# Controller.net
KiCad netlist of a schematic drawn in Altium Designer
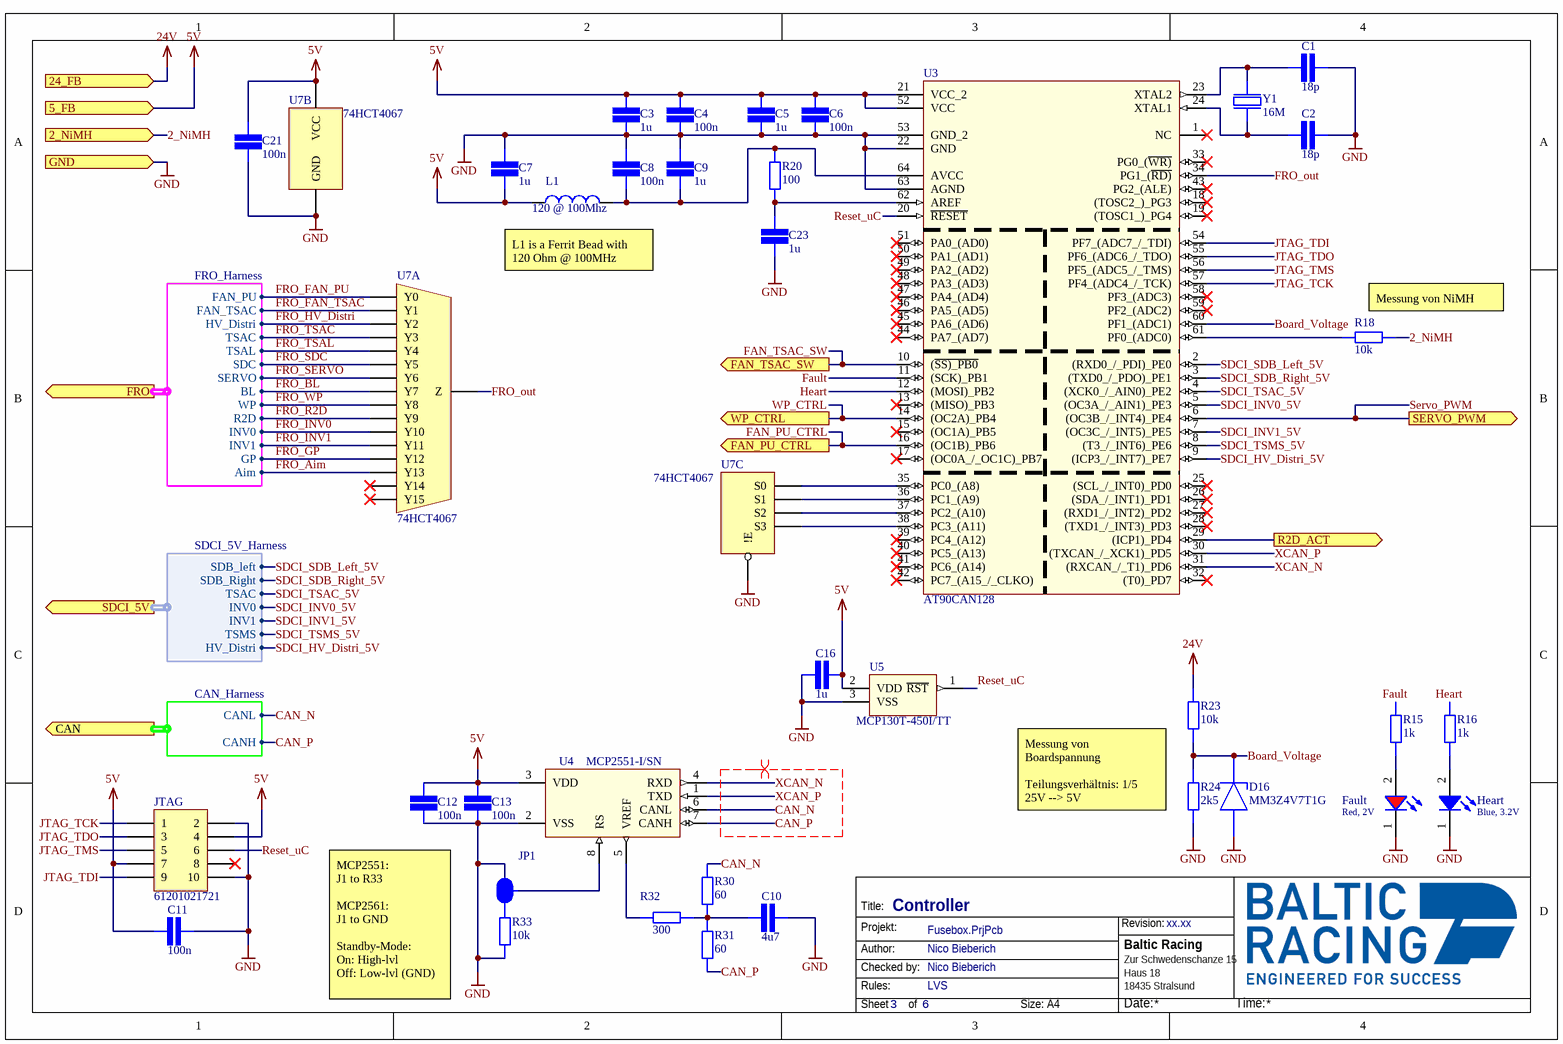
[diagram p0: Controller.SchDoc]

(export (version "E")
  (design (tool "Eeschema 10.0.6"))
  (components
    (comp (ref "C1")
      (value "18p")
      (footprint "CAP 0603/1608")
      (description "Capacitor with multiple Footprints")
      (fields (field (name "VOLTAGE") "16") (field (name "Comment") "SMD Capacitor"))
      (libsource (lib "") (part "SMD Capacitor_1"))
    )
    (comp (ref "C2")
      (value "18p")
      (footprint "CAP 0603/1608")
      (description "Capacitor with multiple Footprints")
      (fields (field (name "VOLTAGE") "16") (field (name "Comment") "SMD Capacitor"))
      (libsource (lib "") (part "SMD Capacitor_1"))
    )
    (comp (ref "C3")
      (value "1u")
      (footprint "CAP 0603/1608")
      (description "Capacitor with multiple Footprints")
      (fields (field (name "VOLTAGE") "16") (field (name "Comment") "SMD Capacitor"))
      (libsource (lib "Standardbauteile") (part "SMD Capacitor"))
    )
    (comp (ref "C4")
      (value "100n")
      (footprint "CAP 0603/1608")
      (description "Capacitor with multiple Footprints")
      (fields (field (name "VOLTAGE") "16") (field (name "Comment") "SMD Capacitor"))
      (libsource (lib "Standardbauteile") (part "SMD Capacitor"))
    )
    (comp (ref "C5")
      (value "1u")
      (footprint "CAP 0603/1608")
      (description "Capacitor with multiple Footprints")
      (fields (field (name "VOLTAGE") "16") (field (name "Comment") "SMD Capacitor"))
      (libsource (lib "Standardbauteile") (part "SMD Capacitor"))
    )
    (comp (ref "C6")
      (value "100n")
      (footprint "CAP 0603/1608")
      (description "Capacitor with multiple Footprints")
      (fields (field (name "VOLTAGE") "16") (field (name "Comment") "SMD Capacitor"))
      (libsource (lib "Standardbauteile") (part "SMD Capacitor"))
    )
    (comp (ref "C7")
      (value "1u")
      (footprint "CAP 0603/1608")
      (description "Capacitor with multiple Footprints")
      (fields (field (name "VOLTAGE") "16") (field (name "Comment") "SMD Capacitor"))
      (libsource (lib "Standardbauteile") (part "SMD Capacitor"))
    )
    (comp (ref "C8")
      (value "100n")
      (footprint "CAP 0603/1608")
      (description "Capacitor with multiple Footprints")
      (fields (field (name "VOLTAGE") "16") (field (name "Comment") "SMD Capacitor"))
      (libsource (lib "Standardbauteile") (part "SMD Capacitor"))
    )
    (comp (ref "C9")
      (value "1u")
      (footprint "CAP 0603/1608")
      (description "Capacitor with multiple Footprints")
      (fields (field (name "VOLTAGE") "16") (field (name "Comment") "SMD Capacitor"))
      (libsource (lib "Standardbauteile") (part "SMD Capacitor"))
    )
    (comp (ref "C10")
      (value "4u7")
      (footprint "CAP 0603/1608")
      (description "Capacitor with multiple Footprints")
      (fields (field (name "VOLTAGE") "16") (field (name "Comment") "SMD Capacitor"))
      (libsource (lib "") (part "SMD Capacitor_2"))
    )
    (comp (ref "C11")
      (value "100n")
      (footprint "CAP 0603/1608")
      (description "Capacitor with multiple Footprints")
      (fields (field (name "VOLTAGE") "16") (field (name "Comment") "SMD Capacitor"))
      (libsource (lib "") (part "SMD Capacitor_1"))
    )
    (comp (ref "C12")
      (value "100n")
      (footprint "CAP 0603/1608")
      (description "Capacitor with multiple Footprints")
      (fields (field (name "VOLTAGE") "16") (field (name "Comment") "SMD Capacitor"))
      (libsource (lib "Standardbauteile") (part "SMD Capacitor"))
    )
    (comp (ref "C13")
      (value "100n")
      (footprint "CAP 0603/1608")
      (description "Capacitor with multiple Footprints")
      (fields (field (name "VOLTAGE") "16") (field (name "Comment") "SMD Capacitor"))
      (libsource (lib "Standardbauteile") (part "SMD Capacitor"))
    )
    (comp (ref "C16")
      (value "1u")
      (footprint "CAP 0603/1608")
      (description "Capacitor with multiple Footprints")
      (fields (field (name "VOLTAGE") "16") (field (name "Comment") "SMD Capacitor"))
      (libsource (lib "") (part "SMD Capacitor_1"))
    )
    (comp (ref "C21")
      (value "100n")
      (footprint "CAP 0603/1608")
      (description "Capacitor with multiple Footprints")
      (fields (field (name "VOLTAGE") "16") (field (name "Comment") "SMD Capacitor"))
      (libsource (lib "Standardbauteile") (part "SMD Capacitor"))
    )
    (comp (ref "C23")
      (value "1u")
      (footprint "CAP 0603/1608")
      (description "Capacitor with multiple Footprints")
      (fields (field (name "VOLTAGE") "16") (field (name "Comment") "SMD Capacitor"))
      (libsource (lib "Standardbauteile") (part "SMD Capacitor"))
    )
    (comp (ref "D16")
      (value "MM3Z4V7T1G")
      (footprint "SOD-323-2")
      (description "onsemi MM3Z4V7T1G\r\nZ-Diode, 4,7V")
      (libsource (lib "libNico") (part "MM3Z4V7T1G"))
    )
    (comp (ref "Fault")
      (value "Red, 2V")
      (footprint "WL-SMCW_0603_H=0.7mm")
      (description "WL-SMCW SMT Mono-color Chip LED Waterclear, size 0603, Red, 2V, 140deg")
      (fields (field (name "PART NUMBER") "150060RS75000") (field (name "PUBLISHER") "Wurth Elektronik"))
      (libsource (lib "Altium_WL-SMCW (rev20a)") (part "150060RS75000"))
    )
    (comp (ref "Heart")
      (value "Blue, 3.2V")
      (footprint "WL-SMCW_0603_H=0.7mm")
      (description "WL-SMCW SMT Mono-color Chip LED Waterclear, size 0603, Blue, 3.2V, 140deg")
      (fields (field (name "PART NUMBER") "150060BS75000") (field (name "PUBLISHER") "Wurth Elektronik"))
      (libsource (lib "Altium_WL-SMCW (rev20a)") (part "150060BS75000"))
    )
    (comp (ref "JP1")
      (value "JUMPERID")
      (footprint "SMD-JUMPER-3")
      (libsource (lib "Standardbauteile") (part "SMD Jumper 3"))
    )
    (comp (ref "JTAG")
      (value "61201021721")
      (footprint "61201021721")
      (description "WR-BHD 2.54mm Male Angled Box Header")
      (fields (field (name "MANUFACTURER") "Wurth Elektronik") (field (name "CREATED BY") "Baojun Chen"))
      (libsource (lib "ALTIUM-BHD_2_54_MALE_BOX_HEADER_6120XX21621-rev16b") (part "61201021721"))
    )
    (comp (ref "L1")
      (value "120 @ 100Mhz")
      (footprint "WE-CBA_0603_L1.6W0.8H0.8_HF/HS/WB")
      (description "WE-CBA SMT EMI Suppression Ferrite Bead, size 0603, 120Ohm, 0.5A")
      (fields
        (field (name "MANUFACTURER PART NUMBER") "782631131")
        (field (name "MANUFACTURER") "Wurth Elektronik")
      )
      (libsource (lib "Altium_WE-CBA (rev22d)") (part "782631131"))
    )
    (comp (ref "R15")
      (value "1k")
      (footprint "STACKPOLE CSR0603")
      (description "Resistor with multiple footprints")
      (fields (field (name "POWER") "0.1W") (field (name "Comment") "SMD Resistor"))
      (libsource (lib "Standardbauteile") (part "SMD Resistor"))
    )
    (comp (ref "R16")
      (value "1k")
      (footprint "STACKPOLE CSR0603")
      (description "Resistor with multiple footprints")
      (fields (field (name "POWER") "0.1W") (field (name "Comment") "SMD Resistor"))
      (libsource (lib "Standardbauteile") (part "SMD Resistor"))
    )
    (comp (ref "R18")
      (value "10k")
      (footprint "STACKPOLE CSR0603")
      (description "Resistor with multiple footprints")
      (fields (field (name "POWER") "0.1W") (field (name "Comment") "SMD Resistor"))
      (libsource (lib "Standardbauteile") (part "SMD Resistor"))
    )
    (comp (ref "R20")
      (value "100")
      (footprint "STACKPOLE CSR0603")
      (description "Resistor with multiple footprints")
      (fields (field (name "POWER") "0.1W") (field (name "Comment") "SMD Resistor"))
      (libsource (lib "Standardbauteile") (part "SMD Resistor"))
    )
    (comp (ref "R23")
      (value "10k")
      (footprint "STACKPOLE CSR0603")
      (description "Resistor with multiple footprints")
      (fields (field (name "POWER") "0.1W") (field (name "Comment") "SMD Resistor"))
      (libsource (lib "Standardbauteile") (part "SMD Resistor"))
    )
    (comp (ref "R24")
      (value "2k5")
      (footprint "STACKPOLE CSR0603")
      (description "Resistor with multiple footprints")
      (fields (field (name "POWER") "0.1W") (field (name "Comment") "SMD Resistor"))
      (libsource (lib "Standardbauteile") (part "SMD Resistor"))
    )
    (comp (ref "R30")
      (value "60")
      (footprint "STACKPOLE CSR0603")
      (description "Resistor with multiple footprints")
      (fields (field (name "POWER") "0.1W") (field (name "Comment") "SMD Resistor"))
      (libsource (lib "Standardbauteile") (part "SMD Resistor"))
    )
    (comp (ref "R31")
      (value "60")
      (footprint "STACKPOLE CSR0603")
      (description "Resistor with multiple footprints")
      (fields (field (name "POWER") "0.1W") (field (name "Comment") "SMD Resistor"))
      (libsource (lib "Standardbauteile") (part "SMD Resistor"))
    )
    (comp (ref "R32")
      (value "300")
      (footprint "STACKPOLE CSR0603")
      (description "Resistor with multiple footprints")
      (fields (field (name "POWER") "0.1W") (field (name "Comment") "SMD Resistor"))
      (libsource (lib "Standardbauteile") (part "SMD Resistor"))
    )
    (comp (ref "R33")
      (value "10k")
      (footprint "STACKPOLE CSR0603")
      (description "Resistor with multiple footprints")
      (fields (field (name "POWER") "0.1W") (field (name "Comment") "SMD Resistor"))
      (libsource (lib "Standardbauteile") (part "SMD Resistor"))
    )
    (comp (ref "U3")
      (value "AT90CAN128")
      (footprint "*QFP80P1600X1600X120-64N")
      (description "Ic Mcu 8bit 128kb Flash 64tqfp")
      (fields (field (name "MP") "AT90CAN128-16AI") (field (name "MF") "Microchip"))
      (libsource (lib "Eric") (part "AT90CAN128"))
    )
    (comp (ref "U4")
      (value "MCP2551-I/SN")
      (footprint "*SOIC127P600X175-8N")
      (description "MCP2551 Series 5.5 V 1 Mb/s Surface Mount High-Speed CAN Transceiver - SOIC-8")
      (fields (field (name "MF") "Microchip"))
      (libsource (lib "Eric") (part "MCP2551-I/SN"))
    )
    (comp (ref "U5")
      (value "MCP130T-450I/TT")
      (footprint "*SOT95P237X112-3N")
      (description "System Supervisors - Power Supply Monitors with Reset Generators Open Drain Low")
      (fields (field (name "MF") "Microchip") (field (name "MP") "MCP120T-450I/TT"))
      (libsource (lib "Eric") (part "MCP130T-450I/TT"))
    )
    (comp (ref "U7")
      (value "74HCT4067")
      (footprint "74HCT4067PW")
      (description "Nexperia 74HCT4067\r\n16-channel analog multiplexer")
      (libsource (lib "libNico") (part "74HCT4067"))
    )
    (comp (ref "Y1")
      (value "16M")
      (footprint "NDK NX5032GA")
      (description "16 MHz Quartz")
      (libsource (lib "Standardbauteile") (part "16 MHz Quartz"))
    )
  )
  (nets
    (net (code "4") (name "/2_NiMH") (class "Default")
      (node (ref "R18") (pin "2") (pinfunction "2_2") (pintype "passive"))
    )
    (net (code "6") (name "/Board_Voltage") (class "Default")
      (node (ref "D16") (pin "1C") (pinfunction "C_1C") (pintype "passive"))
      (node (ref "R23") (pin "1") (pinfunction "1_1") (pintype "passive"))
      (node (ref "R24") (pin "2") (pinfunction "2_2") (pintype "passive"))
      (node (ref "U3") (pin "60") (pinfunction "PF1_(ADC1)_60") (pintype "bidirectional"))
    )
    (net (code "7") (name "/CAN_N") (class "Default")
      (node (ref "R30") (pin "1") (pinfunction "1_1") (pintype "passive"))
      (node (ref "U4") (pin "6") (pinfunction "CANL_6") (pintype "bidirectional"))
    )
    (net (code "8") (name "/CAN_P") (class "Default")
      (node (ref "R31") (pin "2") (pinfunction "2_2") (pintype "passive"))
      (node (ref "U4") (pin "7") (pinfunction "CANH_7") (pintype "bidirectional"))
    )
    (net (code "9") (name "/FAN_PU_CTRL") (class "Default")
      (node (ref "U3") (pin "16") (pinfunction "(OC1B)_PB6_16") (pintype "bidirectional"))
    )
    (net (code "10") (name "/FAN_TSAC_SW") (class "Default")
      (node (ref "U3") (pin "10") (pinfunction "(~{SS)_PB0}_10") (pintype "bidirectional"))
    )
    (net (code "11") (name "/FRO_Aim") (class "Default")
      (node (ref "U7") (pin "18") (pinfunction "Y13_18") (pintype "passive"))
    )
    (net (code "12") (name "/FRO_BL") (class "Default")
      (node (ref "U7") (pin "2") (pinfunction "Y7_2") (pintype "passive"))
    )
    (net (code "13") (name "/FRO_FAN_PU") (class "Default")
      (node (ref "U7") (pin "9") (pinfunction "Y0_9") (pintype "passive"))
    )
    (net (code "14") (name "/FRO_FAN_TSAC") (class "Default")
      (node (ref "U7") (pin "8") (pinfunction "Y1_8") (pintype "passive"))
    )
    (net (code "15") (name "/FRO_GP") (class "Default")
      (node (ref "U7") (pin "19") (pinfunction "Y12_19") (pintype "passive"))
    )
    (net (code "16") (name "/FRO_HV_Distri") (class "Default")
      (node (ref "U7") (pin "7") (pinfunction "Y2_7") (pintype "passive"))
    )
    (net (code "17") (name "/FRO_INV0") (class "Default")
      (node (ref "U7") (pin "21") (pinfunction "Y10_21") (pintype "passive"))
    )
    (net (code "18") (name "/FRO_INV1") (class "Default")
      (node (ref "U7") (pin "20") (pinfunction "Y11_20") (pintype "passive"))
    )
    (net (code "19") (name "/FRO_R2D") (class "Default")
      (node (ref "U7") (pin "22") (pinfunction "Y9_22") (pintype "passive"))
    )
    (net (code "20") (name "/FRO_SDC") (class "Default")
      (node (ref "U7") (pin "4") (pinfunction "Y5_4") (pintype "passive"))
    )
    (net (code "21") (name "/FRO_SERVO") (class "Default")
      (node (ref "U7") (pin "3") (pinfunction "Y6_3") (pintype "passive"))
    )
    (net (code "22") (name "/FRO_TSAC") (class "Default")
      (node (ref "U7") (pin "6") (pinfunction "Y3_6") (pintype "passive"))
    )
    (net (code "23") (name "/FRO_TSAL") (class "Default")
      (node (ref "U7") (pin "5") (pinfunction "Y4_5") (pintype "passive"))
    )
    (net (code "24") (name "/FRO_WP") (class "Default")
      (node (ref "U7") (pin "23") (pinfunction "Y8_23") (pintype "passive"))
    )
    (net (code "25") (name "/FRO_out") (class "Default")
      (node (ref "U3") (pin "34") (pinfunction "PG1_(~{RD)}_34") (pintype "bidirectional"))
      (node (ref "U7") (pin "1") (pinfunction "Z_1") (pintype "passive"))
    )
    (net (code "26") (name "/Fault") (class "Default")
      (node (ref "R15") (pin "1") (pinfunction "1_1") (pintype "passive"))
      (node (ref "U3") (pin "11") (pinfunction "(SCK)_PB1_11") (pintype "bidirectional"))
    )
    (net (code "27") (name "/Heart") (class "Default")
      (node (ref "R16") (pin "1") (pinfunction "1_1") (pintype "passive"))
      (node (ref "U3") (pin "12") (pinfunction "(MOSI)_PB2_12") (pintype "bidirectional"))
    )
    (net (code "28") (name "/JTAG_TCK") (class "Default")
      (node (ref "JTAG") (pin "1") (pinfunction "1_1") (pintype "passive"))
      (node (ref "U3") (pin "57") (pinfunction "PF4_(ADC4_/_TCK)_57") (pintype "bidirectional"))
    )
    (net (code "29") (name "/JTAG_TDI") (class "Default")
      (node (ref "JTAG") (pin "9") (pinfunction "9_9") (pintype "passive"))
      (node (ref "U3") (pin "54") (pinfunction "PF7_(ADC7_/_TDI)_54") (pintype "bidirectional"))
    )
    (net (code "30") (name "/JTAG_TDO") (class "Default")
      (node (ref "JTAG") (pin "3") (pinfunction "3_3") (pintype "passive"))
      (node (ref "U3") (pin "55") (pinfunction "PF6_(ADC6_/_TDO)_55") (pintype "bidirectional"))
    )
    (net (code "31") (name "/JTAG_TMS") (class "Default")
      (node (ref "JTAG") (pin "5") (pinfunction "5_5") (pintype "passive"))
      (node (ref "U3") (pin "56") (pinfunction "PF5_(ADC5_/_TMS)_56") (pintype "bidirectional"))
    )
    (net (code "32") (name "/R2D_ACT") (class "Default")
      (node (ref "U3") (pin "29") (pinfunction "(ICP1)_PD4_29") (pintype "bidirectional"))
    )
    (net (code "33") (name "/Reset_uC") (class "Default")
      (node (ref "JTAG") (pin "6") (pinfunction "6_6") (pintype "passive"))
      (node (ref "U3") (pin "20") (pinfunction "~{RESET}_20") (pintype "input"))
      (node (ref "U5") (pin "1") (pinfunction "~{RST}_1") (pintype "output"))
    )
    (net (code "34") (name "/SDCI_HV_Distri_5V") (class "Default")
      (node (ref "U3") (pin "9") (pinfunction "(ICP3_/_INT7)_PE7_9") (pintype "bidirectional"))
    )
    (net (code "35") (name "/SDCI_INV0_5V") (class "Default")
      (node (ref "U3") (pin "5") (pinfunction "(OC3A_/_AIN1)_PE3_5") (pintype "bidirectional"))
    )
    (net (code "36") (name "/SDCI_INV1_5V") (class "Default")
      (node (ref "U3") (pin "7") (pinfunction "(OC3C_/_INT5)_PE5_7") (pintype "bidirectional"))
    )
    (net (code "37") (name "/SDCI_SDB_Left_5V") (class "Default")
      (node (ref "U3") (pin "2") (pinfunction "(RXD0_/_PDI)_PE0_2") (pintype "bidirectional"))
    )
    (net (code "38") (name "/SDCI_SDB_Right_5V") (class "Default")
      (node (ref "U3") (pin "3") (pinfunction "(TXD0_/_PDO)_PE1_3") (pintype "bidirectional"))
    )
    (net (code "39") (name "/SDCI_TSAC_5V") (class "Default")
      (node (ref "U3") (pin "4") (pinfunction "(XCK0_/_AIN0)_PE2_4") (pintype "bidirectional"))
    )
    (net (code "40") (name "/SDCI_TSMS_5V") (class "Default")
      (node (ref "U3") (pin "8") (pinfunction "(T3_/_INT6)_PE6_8") (pintype "bidirectional"))
    )
    (net (code "41") (name "/Servo_PWM") (class "Default")
      (node (ref "U3") (pin "6") (pinfunction "(OC3B_/_INT4)_PE4_6") (pintype "bidirectional"))
    )
    (net (code "42") (name "/WP_CTRL") (class "Default")
      (node (ref "U3") (pin "14") (pinfunction "(OC2A)_PB4_14") (pintype "bidirectional"))
    )
    (net (code "43") (name "/XCAN_N") (class "Default")
      (node (ref "U3") (pin "31") (pinfunction "(RXCAN_/_T1)_PD6_31") (pintype "bidirectional"))
      (node (ref "U4") (pin "4") (pinfunction "RXD_4") (pintype "output"))
    )
    (net (code "44") (name "/XCAN_P") (class "Default")
      (node (ref "U3") (pin "30") (pinfunction "(TXCAN_/_XCK1)_PD5_30") (pintype "bidirectional"))
      (node (ref "U4") (pin "1") (pinfunction "TXD_1") (pintype "input"))
    )
    (net (code "48") (name "5V") (class "Default")
      (node (ref "C11") (pin "2") (pinfunction "2_2") (pintype "passive"))
      (node (ref "C12") (pin "2") (pinfunction "2_2") (pintype "passive"))
      (node (ref "C13") (pin "2") (pinfunction "2_2") (pintype "passive"))
      (node (ref "C16") (pin "1") (pinfunction "1_1") (pintype "passive"))
      (node (ref "C21") (pin "2") (pinfunction "2_2") (pintype "passive"))
      (node (ref "C3") (pin "2") (pinfunction "2_2") (pintype "passive"))
      (node (ref "C4") (pin "2") (pinfunction "2_2") (pintype "passive"))
      (node (ref "C5") (pin "2") (pinfunction "2_2") (pintype "passive"))
      (node (ref "C6") (pin "2") (pinfunction "2_2") (pintype "passive"))
      (node (ref "C7") (pin "1") (pinfunction "1_1") (pintype "passive"))
      (node (ref "JTAG") (pin "4") (pinfunction "4_4") (pintype "passive"))
      (node (ref "JTAG") (pin "7") (pinfunction "7_7") (pintype "passive"))
      (node (ref "L1") (pin "1") (pinfunction "1_1") (pintype "passive"))
      (node (ref "U3") (pin "21") (pinfunction "VCC_2_21") (pintype "power_in"))
      (node (ref "U3") (pin "52") (pinfunction "VCC_52") (pintype "power_in"))
      (node (ref "U4") (pin "3") (pinfunction "VDD_3") (pintype "power_in"))
      (node (ref "U5") (pin "2") (pinfunction "VDD_2") (pintype "power_in"))
      (node (ref "U7") (pin "24") (pinfunction "VCC_24") (pintype "passive"))
    )
    (net (code "49") (name "24V") (class "Default")
      (node (ref "R23") (pin "2") (pinfunction "2_2") (pintype "passive"))
    )
    (net (code "50") (name "GND") (class "Default")
      (node (ref "C1") (pin "1") (pinfunction "1_1") (pintype "passive"))
      (node (ref "C10") (pin "2") (pinfunction "2_2") (pintype "passive"))
      (node (ref "C11") (pin "1") (pinfunction "1_1") (pintype "passive"))
      (node (ref "C12") (pin "1") (pinfunction "1_1") (pintype "passive"))
      (node (ref "C13") (pin "1") (pinfunction "1_1") (pintype "passive"))
      (node (ref "C16") (pin "2") (pinfunction "2_2") (pintype "passive"))
      (node (ref "C2") (pin "1") (pinfunction "1_1") (pintype "passive"))
      (node (ref "C21") (pin "1") (pinfunction "1_1") (pintype "passive"))
      (node (ref "C23") (pin "1") (pinfunction "1_1") (pintype "passive"))
      (node (ref "C3") (pin "1") (pinfunction "1_1") (pintype "passive"))
      (node (ref "C4") (pin "1") (pinfunction "1_1") (pintype "passive"))
      (node (ref "C5") (pin "1") (pinfunction "1_1") (pintype "passive"))
      (node (ref "C6") (pin "1") (pinfunction "1_1") (pintype "passive"))
      (node (ref "C7") (pin "2") (pinfunction "2_2") (pintype "passive"))
      (node (ref "C8") (pin "2") (pinfunction "2_2") (pintype "passive"))
      (node (ref "C9") (pin "2") (pinfunction "2_2") (pintype "passive"))
      (node (ref "D16") (pin "2A") (pinfunction "A_2A") (pintype "passive"))
      (node (ref "Fault") (pin "1") (pinfunction "K_1") (pintype "passive"))
      (node (ref "Heart") (pin "1") (pinfunction "K_1") (pintype "passive"))
      (node (ref "JP1") (pin "1") (pinfunction "1_1") (pintype "passive"))
      (node (ref "JTAG") (pin "10") (pinfunction "10_10") (pintype "passive"))
      (node (ref "JTAG") (pin "2") (pinfunction "2_2") (pintype "passive"))
      (node (ref "R24") (pin "1") (pinfunction "1_1") (pintype "passive"))
      (node (ref "R33") (pin "1") (pinfunction "1_1") (pintype "passive"))
      (node (ref "U3") (pin "22") (pinfunction "GND_22") (pintype "passive"))
      (node (ref "U3") (pin "53") (pinfunction "GND_2_53") (pintype "passive"))
      (node (ref "U3") (pin "63") (pinfunction "AGND_63") (pintype "passive"))
      (node (ref "U4") (pin "2") (pinfunction "VSS_2") (pintype "passive"))
      (node (ref "U5") (pin "3") (pinfunction "VSS_3") (pintype "power_in"))
      (node (ref "U7") (pin "12") (pinfunction "GND_12") (pintype "passive"))
      (node (ref "U7") (pin "15") (pinfunction "!E_15") (pintype "passive"))
    )
    (net (code "51") (name "Net-(C10-Pad1)") (class "Default")
      (node (ref "C10") (pin "1") (pinfunction "1_1") (pintype "passive"))
      (node (ref "R30") (pin "2") (pinfunction "2_2") (pintype "passive"))
      (node (ref "R31") (pin "1") (pinfunction "1_1") (pintype "passive"))
      (node (ref "R32") (pin "2") (pinfunction "2_2") (pintype "passive"))
    )
    (net (code "52") (name "Net-(Fault-A)") (class "Default")
      (node (ref "Fault") (pin "2") (pinfunction "A_2") (pintype "passive"))
      (node (ref "R15") (pin "2") (pinfunction "2_2") (pintype "passive"))
    )
    (net (code "53") (name "Net-(Heart-A)") (class "Default")
      (node (ref "Heart") (pin "2") (pinfunction "A_2") (pintype "passive"))
      (node (ref "R16") (pin "2") (pinfunction "2_2") (pintype "passive"))
    )
    (net (code "54") (name "Net-(JP1-Pad3)") (class "Default")
      (node (ref "JP1") (pin "3") (pinfunction "3_3") (pintype "passive"))
      (node (ref "R33") (pin "2") (pinfunction "2_2") (pintype "passive"))
    )
    (net (code "55") (name "Net-(U3-AREF)") (class "Default")
      (node (ref "C23") (pin "2") (pinfunction "2_2") (pintype "passive"))
      (node (ref "R20") (pin "1") (pinfunction "1_1") (pintype "passive"))
      (node (ref "U3") (pin "62") (pinfunction "AREF_62") (pintype "input"))
    )
    (net (code "56") (name "Net-(U3-AVCC)") (class "Default")
      (node (ref "C8") (pin "1") (pinfunction "1_1") (pintype "passive"))
      (node (ref "C9") (pin "1") (pinfunction "1_1") (pintype "passive"))
      (node (ref "L1") (pin "2") (pinfunction "2_2") (pintype "passive"))
      (node (ref "R20") (pin "2") (pinfunction "2_2") (pintype "passive"))
      (node (ref "U3") (pin "64") (pinfunction "AVCC_64") (pintype "power_in"))
    )
    (net (code "57") (name "Net-(U3-PC0_(A8))") (class "Default")
      (node (ref "U3") (pin "35") (pinfunction "PC0_(A8)_35") (pintype "bidirectional"))
      (node (ref "U7") (pin "10") (pinfunction "S0_10") (pintype "passive"))
    )
    (net (code "58") (name "Net-(U3-PC1_(A9))") (class "Default")
      (node (ref "U3") (pin "36") (pinfunction "PC1_(A9)_36") (pintype "bidirectional"))
      (node (ref "U7") (pin "11") (pinfunction "S1_11") (pintype "passive"))
    )
    (net (code "59") (name "Net-(U3-PC2_(A10))") (class "Default")
      (node (ref "U3") (pin "37") (pinfunction "PC2_(A10)_37") (pintype "bidirectional"))
      (node (ref "U7") (pin "14") (pinfunction "S2_14") (pintype "passive"))
    )
    (net (code "60") (name "Net-(U3-PC3_(A11))") (class "Default")
      (node (ref "U3") (pin "38") (pinfunction "PC3_(A11)_38") (pintype "bidirectional"))
      (node (ref "U7") (pin "13") (pinfunction "S3_13") (pintype "passive"))
    )
    (net (code "61") (name "Net-(U3-PF0_(ADC0))") (class "Default")
      (node (ref "R18") (pin "1") (pinfunction "1_1") (pintype "passive"))
      (node (ref "U3") (pin "61") (pinfunction "PF0_(ADC0)_61") (pintype "bidirectional"))
    )
    (net (code "62") (name "Net-(U3-XTAL1)") (class "Default")
      (node (ref "C2") (pin "2") (pinfunction "2_2") (pintype "passive"))
      (node (ref "U3") (pin "24") (pinfunction "XTAL1_24") (pintype "input"))
      (node (ref "Y1") (pin "1") (pinfunction "1_1") (pintype "passive"))
    )
    (net (code "63") (name "Net-(U3-XTAL2)") (class "Default")
      (node (ref "C1") (pin "2") (pinfunction "2_2") (pintype "passive"))
      (node (ref "U3") (pin "23") (pinfunction "XTAL2_23") (pintype "output"))
      (node (ref "Y1") (pin "2") (pinfunction "2_2") (pintype "passive"))
    )
    (net (code "64") (name "Net-(U4-RS)") (class "Default")
      (node (ref "JP1") (pin "2") (pinfunction "2_2") (pintype "passive"))
      (node (ref "U4") (pin "8") (pinfunction "RS_8") (pintype "input"))
    )
    (net (code "65") (name "Net-(U4-VREF)") (class "Default")
      (node (ref "R32") (pin "1") (pinfunction "1_1") (pintype "passive"))
      (node (ref "U4") (pin "5") (pinfunction "VREF_5") (pintype "output"))
    )
    (net (code "66") (name "unconnected-(JTAG-Pad8)") (class "Default")
      (node (ref "JTAG") (pin "8") (pinfunction "8_8") (pintype "passive+no_connect"))
    )
    (net (code "67") (name "unconnected-(U3-(MISO)_PB3-Pad13)") (class "Default")
      (node (ref "U3") (pin "13") (pinfunction "(MISO)_PB3_13") (pintype "bidirectional+no_connect"))
    )
    (net (code "68") (name "unconnected-(U3-(OC0A_{slash}_OC1C)_PB7-Pad17)") (class "Default")
      (node (ref "U3") (pin "17") (pinfunction "(OC0A_/_OC1C)_PB7_17") (pintype "bidirectional+no_connect"))
    )
    (net (code "69") (name "unconnected-(U3-(OC1A)_PB5-Pad15)") (class "Default")
      (node (ref "U3") (pin "15") (pinfunction "(OC1A)_PB5_15") (pintype "bidirectional+no_connect"))
    )
    (net (code "70") (name "unconnected-(U3-(RXD1_{slash}_INT2)_PD2-Pad27)") (class "Default")
      (node (ref "U3") (pin "27") (pinfunction "(RXD1_/_INT2)_PD2_27") (pintype "bidirectional+no_connect"))
    )
    (net (code "71") (name "unconnected-(U3-(SCL_{slash}_INT0)_PD0-Pad25)") (class "Default")
      (node (ref "U3") (pin "25") (pinfunction "(SCL_/_INT0)_PD0_25") (pintype "bidirectional+no_connect"))
    )
    (net (code "72") (name "unconnected-(U3-(SDA_{slash}_INT1)_PD1-Pad26)") (class "Default")
      (node (ref "U3") (pin "26") (pinfunction "(SDA_/_INT1)_PD1_26") (pintype "bidirectional+no_connect"))
    )
    (net (code "73") (name "unconnected-(U3-(T0)_PD7-Pad32)") (class "Default")
      (node (ref "U3") (pin "32") (pinfunction "(T0)_PD7_32") (pintype "bidirectional+no_connect"))
    )
    (net (code "74") (name "unconnected-(U3-(TOSC1_)_PG4-Pad19)") (class "Default")
      (node (ref "U3") (pin "19") (pinfunction "(TOSC1_)_PG4_19") (pintype "bidirectional+no_connect"))
    )
    (net (code "75") (name "unconnected-(U3-(TOSC2_)_PG3-Pad18)") (class "Default")
      (node (ref "U3") (pin "18") (pinfunction "(TOSC2_)_PG3_18") (pintype "bidirectional+no_connect"))
    )
    (net (code "76") (name "unconnected-(U3-(TXD1_{slash}_INT3)_PD3-Pad28)") (class "Default")
      (node (ref "U3") (pin "28") (pinfunction "(TXD1_/_INT3)_PD3_28") (pintype "bidirectional+no_connect"))
    )
    (net (code "77") (name "unconnected-(U3-NC-Pad1)") (class "Default")
      (node (ref "U3") (pin "1") (pinfunction "NC_1") (pintype "passive+no_connect"))
    )
    (net (code "78") (name "unconnected-(U3-PA0_(AD0)-Pad51)") (class "Default")
      (node (ref "U3") (pin "51") (pinfunction "PA0_(AD0)_51") (pintype "bidirectional+no_connect"))
    )
    (net (code "79") (name "unconnected-(U3-PA1_(AD1)-Pad50)") (class "Default")
      (node (ref "U3") (pin "50") (pinfunction "PA1_(AD1)_50") (pintype "bidirectional+no_connect"))
    )
    (net (code "80") (name "unconnected-(U3-PA2_(AD2)-Pad49)") (class "Default")
      (node (ref "U3") (pin "49") (pinfunction "PA2_(AD2)_49") (pintype "bidirectional+no_connect"))
    )
    (net (code "81") (name "unconnected-(U3-PA3_(AD3)-Pad48)") (class "Default")
      (node (ref "U3") (pin "48") (pinfunction "PA3_(AD3)_48") (pintype "bidirectional+no_connect"))
    )
    (net (code "82") (name "unconnected-(U3-PA4_(AD4)-Pad47)") (class "Default")
      (node (ref "U3") (pin "47") (pinfunction "PA4_(AD4)_47") (pintype "bidirectional+no_connect"))
    )
    (net (code "83") (name "unconnected-(U3-PA5_(AD5)-Pad46)") (class "Default")
      (node (ref "U3") (pin "46") (pinfunction "PA5_(AD5)_46") (pintype "bidirectional+no_connect"))
    )
    (net (code "84") (name "unconnected-(U3-PA6_(AD6)-Pad45)") (class "Default")
      (node (ref "U3") (pin "45") (pinfunction "PA6_(AD6)_45") (pintype "bidirectional+no_connect"))
    )
    (net (code "85") (name "unconnected-(U3-PA7_(AD7)-Pad44)") (class "Default")
      (node (ref "U3") (pin "44") (pinfunction "PA7_(AD7)_44") (pintype "bidirectional+no_connect"))
    )
    (net (code "86") (name "unconnected-(U3-PC4_(A12)-Pad39)") (class "Default")
      (node (ref "U3") (pin "39") (pinfunction "PC4_(A12)_39") (pintype "bidirectional+no_connect"))
    )
    (net (code "87") (name "unconnected-(U3-PC5_(A13)-Pad40)") (class "Default")
      (node (ref "U3") (pin "40") (pinfunction "PC5_(A13)_40") (pintype "bidirectional+no_connect"))
    )
    (net (code "88") (name "unconnected-(U3-PC6_(A14)-Pad41)") (class "Default")
      (node (ref "U3") (pin "41") (pinfunction "PC6_(A14)_41") (pintype "bidirectional+no_connect"))
    )
    (net (code "89") (name "unconnected-(U3-PC7_(A15_{slash}_CLKO)-Pad42)") (class "Default")
      (node (ref "U3") (pin "42") (pinfunction "PC7_(A15_/_CLKO)_42") (pintype "bidirectional+no_connect"))
    )
    (net (code "90") (name "unconnected-(U3-PF2_(ADC2)-Pad59)") (class "Default")
      (node (ref "U3") (pin "59") (pinfunction "PF2_(ADC2)_59") (pintype "bidirectional+no_connect"))
    )
    (net (code "91") (name "unconnected-(U3-PF3_(ADC3)-Pad58)") (class "Default")
      (node (ref "U3") (pin "58") (pinfunction "PF3_(ADC3)_58") (pintype "bidirectional+no_connect"))
    )
    (net (code "92") (name "unconnected-(U3-PG0_(~{WR)}-Pad33)") (class "Default")
      (node (ref "U3") (pin "33") (pinfunction "PG0_(~{WR)}_33") (pintype "bidirectional+no_connect"))
    )
    (net (code "93") (name "unconnected-(U3-PG2_(ALE)-Pad43)") (class "Default")
      (node (ref "U3") (pin "43") (pinfunction "PG2_(ALE)_43") (pintype "bidirectional+no_connect"))
    )
    (net (code "94") (name "unconnected-(U7A-Y14-Pad17)") (class "Default")
      (node (ref "U7") (pin "17") (pinfunction "Y14_17") (pintype "passive+no_connect"))
    )
    (net (code "95") (name "unconnected-(U7A-Y15-Pad16)") (class "Default")
      (node (ref "U7") (pin "16") (pinfunction "Y15_16") (pintype "passive+no_connect"))
    )
  )
)
